# Lipo_Booster_v1.net
KiCad netlist of a schematic drawn in EAGLE
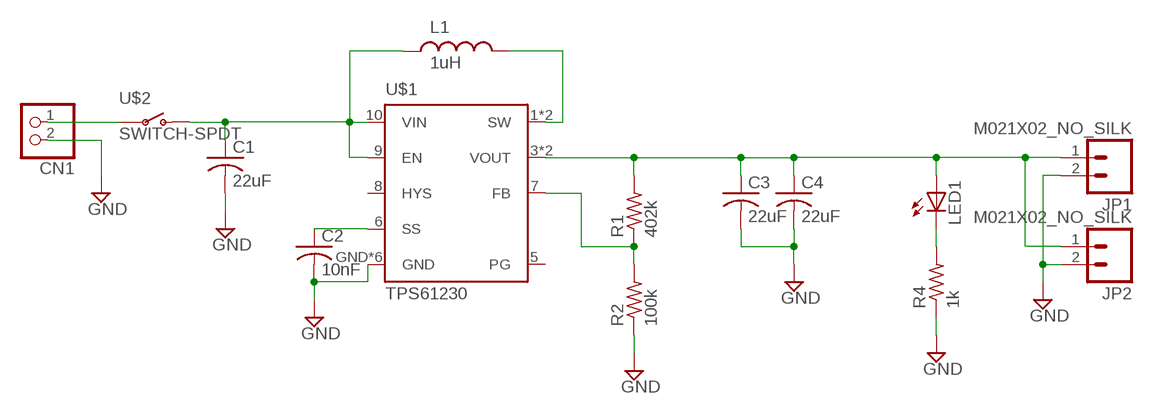
[diagram p0: schematic, sheet 1]

(export (version "E")
  (design (tool "Eeschema 10.0.6"))
  (components
    (comp (ref "C1")
      (value "22uF")
      (footprint "eagle-import:C0603K")
      (libsource (lib "eagle-import") (part "C-USC0603K"))
    )
    (comp (ref "C2")
      (value "10nF")
      (footprint "eagle-import:C0603K")
      (libsource (lib "eagle-import") (part "C-USC0603K"))
    )
    (comp (ref "C3")
      (value "22uF")
      (footprint "eagle-import:C0603K")
      (libsource (lib "eagle-import") (part "C-USC0603K"))
    )
    (comp (ref "C4")
      (value "22uF")
      (footprint "eagle-import:C0603K")
      (libsource (lib "eagle-import") (part "C-USC0603K"))
    )
    (comp (ref "CN1")
      (value "JST_2PIN-SMT-RA")
      (footprint "eagle-import:JST-PH-2-SMT-RA")
      (libsource (lib "eagle-import") (part "JST_2PIN-SMT-RA"))
    )
    (comp (ref "JP1")
      (value "M021X02_NO_SILK")
      (footprint "eagle-import:1X02_NO_SILK")
      (libsource (lib "eagle-import") (part "M021X02_NO_SILK"))
    )
    (comp (ref "JP2")
      (value "M021X02_NO_SILK")
      (footprint "eagle-import:1X02_NO_SILK")
      (libsource (lib "eagle-import") (part "M021X02_NO_SILK"))
    )
    (comp (ref "L1")
      (value "1uH")
      (footprint "eagle-import:XFL4020")
      (libsource (lib "eagle-import") (part "XFL4020"))
    )
    (comp (ref "LED1")
      (value "LEDCHIPLED_0603")
      (footprint "eagle-import:CHIPLED_0603")
      (libsource (lib "eagle-import") (part "LEDCHIPLED_0603"))
    )
    (comp (ref "R1")
      (value "402k")
      (footprint "eagle-import:R0603")
      (libsource (lib "eagle-import") (part "R-US_R0603"))
    )
    (comp (ref "R2")
      (value "100k")
      (footprint "eagle-import:R0603")
      (libsource (lib "eagle-import") (part "R-US_R0603"))
    )
    (comp (ref "R4")
      (value "1k")
      (footprint "eagle-import:R0603")
      (libsource (lib "eagle-import") (part "R-US_R0603"))
    )
    (comp (ref "U$1")
      (value "TPS61230")
      (footprint "eagle-import:DRC-S-PVSON-N11")
      (libsource (lib "eagle-import") (part "TPS61230"))
    )
    (comp (ref "U$2")
      (value "SWITCH-SPDT")
      (footprint "eagle-import:JS102011")
      (libsource (lib "eagle-import") (part "SWITCH-SPDT"))
    )
  )
  (nets
    (net (code "1") (name "/PG") (class "Default")
      (node (ref "U$1") (pin "5") (pinfunction "PG_5") (pintype "power_in"))
    )
    (net (code "2") (name "GND") (class "Default")
      (node (ref "C1") (pin "2") (pinfunction "2_2") (pintype "passive"))
      (node (ref "C2") (pin "2") (pinfunction "2_2") (pintype "passive"))
      (node (ref "C3") (pin "2") (pinfunction "2_2") (pintype "passive"))
      (node (ref "C4") (pin "2") (pinfunction "2_2") (pintype "passive"))
      (node (ref "CN1") (pin "2") (pinfunction "1_2") (pintype "passive"))
      (node (ref "JP1") (pin "2") (pinfunction "2_2") (pintype "passive"))
      (node (ref "JP2") (pin "2") (pinfunction "2_2") (pintype "passive"))
      (node (ref "R2") (pin "1") (pinfunction "1_1") (pintype "passive"))
      (node (ref "R4") (pin "1") (pinfunction "1_1") (pintype "passive"))
      (node (ref "U$1") (pin "GND") (pinfunction "GND_GND") (pintype "power_in"))
      (node (ref "U$1") (pin "GND@1") (pinfunction "GND_GND@1") (pintype "power_in"))
      (node (ref "U$1") (pin "GND@2") (pinfunction "GND_GND@2") (pintype "power_in"))
      (node (ref "U$1") (pin "GND@3") (pinfunction "GND_GND@3") (pintype "power_in"))
      (node (ref "U$1") (pin "GND@4") (pinfunction "GND_GND@4") (pintype "power_in"))
      (node (ref "U$1") (pin "GND@5") (pinfunction "GND_GND@5") (pintype "power_in"))
    )
    (net (code "3") (name "Net-(C3-Pad1)") (class "Default")
      (node (ref "C3") (pin "1") (pinfunction "1_1") (pintype "passive"))
      (node (ref "C4") (pin "1") (pinfunction "1_1") (pintype "passive"))
      (node (ref "JP1") (pin "1") (pinfunction "1_1") (pintype "passive"))
      (node (ref "JP2") (pin "1") (pinfunction "1_1") (pintype "passive"))
      (node (ref "LED1") (pin "A") (pinfunction "A_A") (pintype "passive"))
      (node (ref "R1") (pin "2") (pinfunction "2_2") (pintype "passive"))
      (node (ref "U$1") (pin "3") (pinfunction "VOUT_3") (pintype "passive"))
      (node (ref "U$1") (pin "4") (pinfunction "VOUT_4") (pintype "passive"))
    )
    (net (code "4") (name "Net-(CN1-2)") (class "Default")
      (node (ref "CN1") (pin "1") (pinfunction "2_1") (pintype "passive"))
      (node (ref "U$2") (pin "P$3") (pinfunction "P_P$3") (pintype "passive"))
    )
    (net (code "5") (name "Net-(L1-1)") (class "Default")
      (node (ref "C1") (pin "1") (pinfunction "1_1") (pintype "passive"))
      (node (ref "L1") (pin "P$1") (pinfunction "1_P$1") (pintype "passive"))
      (node (ref "U$1") (pin "10") (pinfunction "VIN_10") (pintype "input"))
      (node (ref "U$1") (pin "9") (pinfunction "EN_9") (pintype "input"))
      (node (ref "U$2") (pin "P$2") (pinfunction "O_P$2") (pintype "passive"))
    )
    (net (code "6") (name "Net-(L1-2)") (class "Default")
      (node (ref "L1") (pin "P$2") (pinfunction "2_P$2") (pintype "passive"))
      (node (ref "U$1") (pin "1") (pinfunction "SW_1") (pintype "input"))
      (node (ref "U$1") (pin "2") (pinfunction "SW_2") (pintype "input"))
    )
    (net (code "7") (name "Net-(LED1-PadC)") (class "Default")
      (node (ref "LED1") (pin "C") (pinfunction "C_C") (pintype "passive"))
      (node (ref "R4") (pin "2") (pinfunction "2_2") (pintype "passive"))
    )
    (net (code "8") (name "Net-(U$1-FB)") (class "Default")
      (node (ref "R1") (pin "1") (pinfunction "1_1") (pintype "passive"))
      (node (ref "R2") (pin "2") (pinfunction "2_2") (pintype "passive"))
      (node (ref "U$1") (pin "7") (pinfunction "FB_7") (pintype "input"))
    )
    (net (code "9") (name "Net-(U$1-SS)") (class "Default")
      (node (ref "C2") (pin "1") (pinfunction "1_1") (pintype "passive"))
      (node (ref "U$1") (pin "6") (pinfunction "SS_6") (pintype "input"))
    )
    (net (code "10") (name "unconnected-(U$1-HYS-Pad8)") (class "Default")
      (node (ref "U$1") (pin "8") (pinfunction "HYS_8") (pintype "input"))
    )
  )
)
